# Pure_Power_Strip.net
KiCad netlist of a schematic drawn in EAGLE
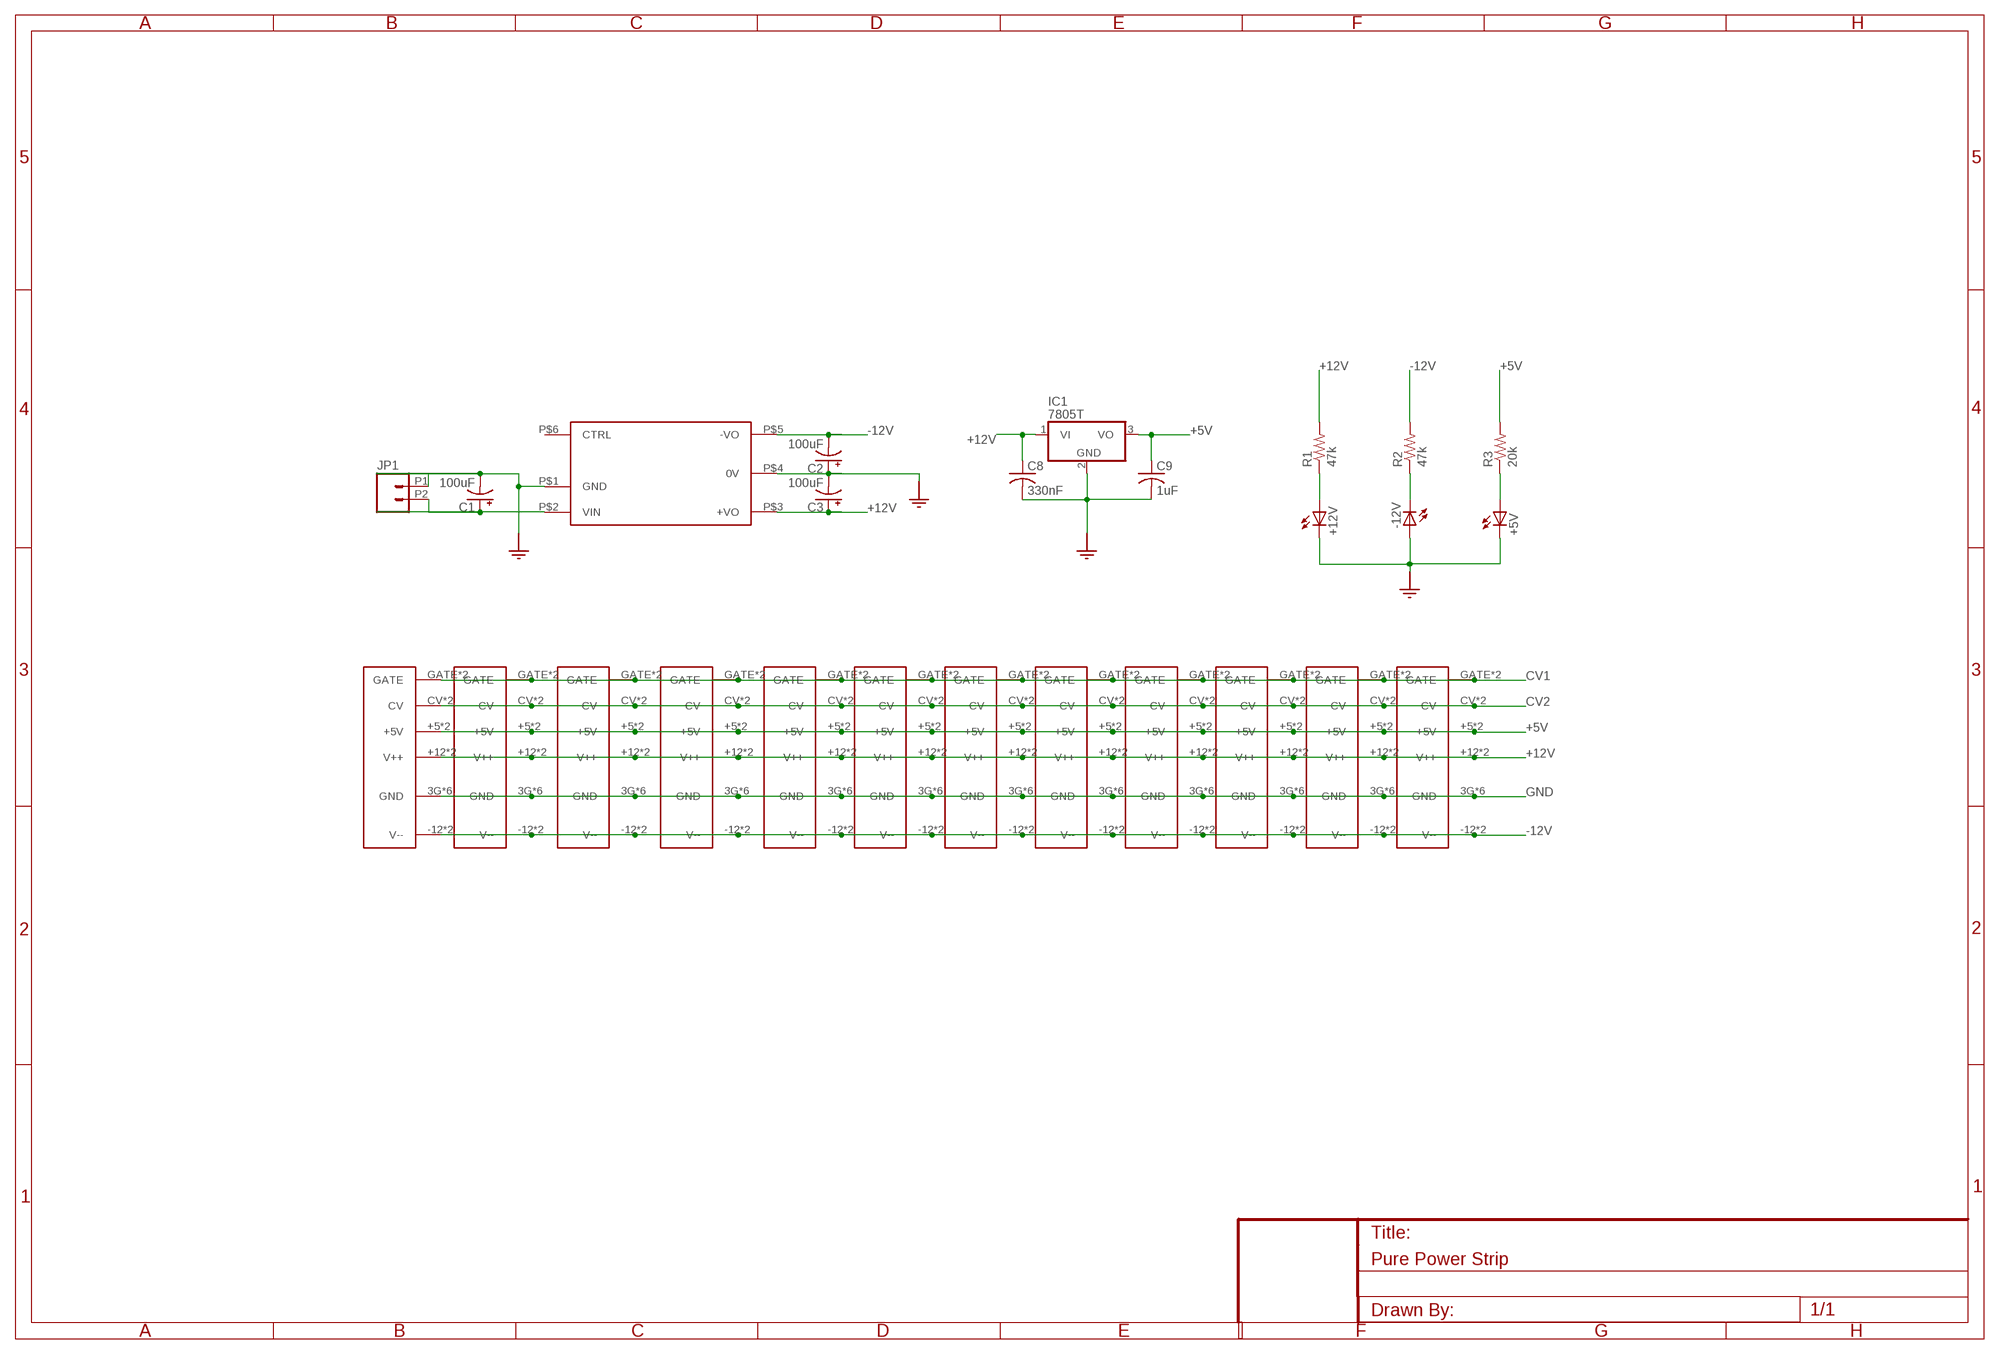
[diagram p0: schematic, sheet 1]

(export (version "E")
  (design (tool "Eeschema 10.0.6"))
  (components
    (comp (ref "+5V")
      (value "LED5MM")
      (footprint "eagle-import:LED5MM")
      (libsource (lib "eagle-import") (part "LED5MM"))
    )
    (comp (ref "+12V")
      (value "LED5MM")
      (footprint "eagle-import:LED5MM")
      (libsource (lib "eagle-import") (part "LED5MM"))
    )
    (comp (ref "-12V")
      (value "LED5MM")
      (footprint "eagle-import:LED5MM")
      (libsource (lib "eagle-import") (part "LED5MM"))
    )
    (comp (ref "C1")
      (value "100uF")
      (footprint "eagle-import:SANYO-OSCON_D")
      (libsource (lib "eagle-import") (part "CPOL-USSANYO_D"))
    )
    (comp (ref "C2")
      (value "100uF")
      (footprint "eagle-import:SANYO-OSCON_D")
      (libsource (lib "eagle-import") (part "CPOL-USSANYO_D"))
    )
    (comp (ref "C3")
      (value "100uF")
      (footprint "eagle-import:SANYO-OSCON_D")
      (libsource (lib "eagle-import") (part "CPOL-USSANYO_D"))
    )
    (comp (ref "C8")
      (value "330nF")
      (footprint "eagle-import:C025-024X044")
      (libsource (lib "eagle-import") (part "C-US025-024X044"))
    )
    (comp (ref "C9")
      (value "1uF")
      (footprint "eagle-import:C025-024X044")
      (libsource (lib "eagle-import") (part "C-US025-024X044"))
    )
    (comp (ref "IC1")
      (value "7805T")
      (footprint "eagle-import:TO220H")
      (libsource (lib "eagle-import") (part "78T05"))
    )
    (comp (ref "JP1")
      (value "1X02_5MM_SCREWTERM")
      (footprint "eagle-import:1X02_5MM_SCREWTERM")
      (libsource (lib "eagle-import") (part "1X02_5MM_SCREWTERM"))
    )
    (comp (ref "R1")
      (value "47k")
      (footprint "eagle-import:0207_10")
      (libsource (lib "eagle-import") (part "R-US_0207/10"))
    )
    (comp (ref "R2")
      (value "47k")
      (footprint "eagle-import:0207_10")
      (libsource (lib "eagle-import") (part "R-US_0207/10"))
    )
    (comp (ref "R3")
      (value "20k")
      (footprint "eagle-import:0207_10")
      (libsource (lib "eagle-import") (part "R-US_0207/10"))
    )
    (comp (ref "U$1")
      (value "URA241XLD-20WR3")
      (footprint "eagle-import:URA241XLD-20WR3")
      (libsource (lib "eagle-import") (part "URA241XLD-20WR3"))
    )
    (comp (ref "U$2")
      (value "EURO_POWER_16")
      (footprint "eagle-import:POWER_SHROUDED")
      (libsource (lib "eagle-import") (part "EURO_POWER_16"))
    )
    (comp (ref "U$3")
      (value "EURO_POWER_16")
      (footprint "eagle-import:POWER_SHROUDED")
      (libsource (lib "eagle-import") (part "EURO_POWER_16"))
    )
    (comp (ref "U$4")
      (value "EURO_POWER_16")
      (footprint "eagle-import:POWER_SHROUDED")
      (libsource (lib "eagle-import") (part "EURO_POWER_16"))
    )
    (comp (ref "U$5")
      (value "EURO_POWER_16")
      (footprint "eagle-import:POWER_SHROUDED")
      (libsource (lib "eagle-import") (part "EURO_POWER_16"))
    )
    (comp (ref "U$6")
      (value "EURO_POWER_16")
      (footprint "eagle-import:POWER_SHROUDED")
      (libsource (lib "eagle-import") (part "EURO_POWER_16"))
    )
    (comp (ref "U$7")
      (value "EURO_POWER_16")
      (footprint "eagle-import:POWER_SHROUDED")
      (libsource (lib "eagle-import") (part "EURO_POWER_16"))
    )
    (comp (ref "U$8")
      (value "EURO_POWER_16")
      (footprint "eagle-import:POWER_SHROUDED")
      (libsource (lib "eagle-import") (part "EURO_POWER_16"))
    )
    (comp (ref "U$9")
      (value "EURO_POWER_16")
      (footprint "eagle-import:POWER_SHROUDED")
      (libsource (lib "eagle-import") (part "EURO_POWER_16"))
    )
    (comp (ref "U$10")
      (value "EURO_POWER_16")
      (footprint "eagle-import:POWER_SHROUDED")
      (libsource (lib "eagle-import") (part "EURO_POWER_16"))
    )
    (comp (ref "U$11")
      (value "EURO_POWER_16")
      (footprint "eagle-import:POWER_SHROUDED")
      (libsource (lib "eagle-import") (part "EURO_POWER_16"))
    )
    (comp (ref "U$12")
      (value "EURO_POWER_16")
      (footprint "eagle-import:POWER_SHROUDED")
      (libsource (lib "eagle-import") (part "EURO_POWER_16"))
    )
    (comp (ref "U$13")
      (value "EURO_POWER_16")
      (footprint "eagle-import:POWER_SHROUDED")
      (libsource (lib "eagle-import") (part "EURO_POWER_16"))
    )
  )
  (nets
    (net (code "1") (name "/+5V") (class "Default")
      (node (ref "C9") (pin "1") (pinfunction "1_1") (pintype "passive"))
      (node (ref "IC1") (pin "3") (pinfunction "VO_3") (pintype "passive"))
      (node (ref "R3") (pin "2") (pinfunction "2_2") (pintype "passive"))
      (node (ref "U$10") (pin "+5") (pinfunction "+5V_+5") (pintype "bidirectional"))
      (node (ref "U$10") (pin "+5A") (pinfunction "+5V_+5A") (pintype "bidirectional"))
      (node (ref "U$11") (pin "+5") (pinfunction "+5V_+5") (pintype "bidirectional"))
      (node (ref "U$11") (pin "+5A") (pinfunction "+5V_+5A") (pintype "bidirectional"))
      (node (ref "U$12") (pin "+5") (pinfunction "+5V_+5") (pintype "bidirectional"))
      (node (ref "U$12") (pin "+5A") (pinfunction "+5V_+5A") (pintype "bidirectional"))
      (node (ref "U$13") (pin "+5") (pinfunction "+5V_+5") (pintype "bidirectional"))
      (node (ref "U$13") (pin "+5A") (pinfunction "+5V_+5A") (pintype "bidirectional"))
      (node (ref "U$2") (pin "+5") (pinfunction "+5V_+5") (pintype "bidirectional"))
      (node (ref "U$2") (pin "+5A") (pinfunction "+5V_+5A") (pintype "bidirectional"))
      (node (ref "U$3") (pin "+5") (pinfunction "+5V_+5") (pintype "bidirectional"))
      (node (ref "U$3") (pin "+5A") (pinfunction "+5V_+5A") (pintype "bidirectional"))
      (node (ref "U$4") (pin "+5") (pinfunction "+5V_+5") (pintype "bidirectional"))
      (node (ref "U$4") (pin "+5A") (pinfunction "+5V_+5A") (pintype "bidirectional"))
      (node (ref "U$5") (pin "+5") (pinfunction "+5V_+5") (pintype "bidirectional"))
      (node (ref "U$5") (pin "+5A") (pinfunction "+5V_+5A") (pintype "bidirectional"))
      (node (ref "U$6") (pin "+5") (pinfunction "+5V_+5") (pintype "bidirectional"))
      (node (ref "U$6") (pin "+5A") (pinfunction "+5V_+5A") (pintype "bidirectional"))
      (node (ref "U$7") (pin "+5") (pinfunction "+5V_+5") (pintype "bidirectional"))
      (node (ref "U$7") (pin "+5A") (pinfunction "+5V_+5A") (pintype "bidirectional"))
      (node (ref "U$8") (pin "+5") (pinfunction "+5V_+5") (pintype "bidirectional"))
      (node (ref "U$8") (pin "+5A") (pinfunction "+5V_+5A") (pintype "bidirectional"))
      (node (ref "U$9") (pin "+5") (pinfunction "+5V_+5") (pintype "bidirectional"))
      (node (ref "U$9") (pin "+5A") (pinfunction "+5V_+5A") (pintype "bidirectional"))
    )
    (net (code "2") (name "/+12V") (class "Default")
      (node (ref "C3") (pin "+") (pinfunction "+_+") (pintype "passive"))
      (node (ref "C8") (pin "1") (pinfunction "1_1") (pintype "passive"))
      (node (ref "IC1") (pin "1") (pinfunction "VI_1") (pintype "input"))
      (node (ref "R1") (pin "2") (pinfunction "2_2") (pintype "passive"))
      (node (ref "U$1") (pin "P$3") (pinfunction "+VO_P$3") (pintype "bidirectional"))
      (node (ref "U$10") (pin "+12") (pinfunction "V++_+12") (pintype "bidirectional"))
      (node (ref "U$10") (pin "+12A") (pinfunction "V++_+12A") (pintype "bidirectional"))
      (node (ref "U$11") (pin "+12") (pinfunction "V++_+12") (pintype "bidirectional"))
      (node (ref "U$11") (pin "+12A") (pinfunction "V++_+12A") (pintype "bidirectional"))
      (node (ref "U$12") (pin "+12") (pinfunction "V++_+12") (pintype "bidirectional"))
      (node (ref "U$12") (pin "+12A") (pinfunction "V++_+12A") (pintype "bidirectional"))
      (node (ref "U$13") (pin "+12") (pinfunction "V++_+12") (pintype "bidirectional"))
      (node (ref "U$13") (pin "+12A") (pinfunction "V++_+12A") (pintype "bidirectional"))
      (node (ref "U$2") (pin "+12") (pinfunction "V++_+12") (pintype "bidirectional"))
      (node (ref "U$2") (pin "+12A") (pinfunction "V++_+12A") (pintype "bidirectional"))
      (node (ref "U$3") (pin "+12") (pinfunction "V++_+12") (pintype "bidirectional"))
      (node (ref "U$3") (pin "+12A") (pinfunction "V++_+12A") (pintype "bidirectional"))
      (node (ref "U$4") (pin "+12") (pinfunction "V++_+12") (pintype "bidirectional"))
      (node (ref "U$4") (pin "+12A") (pinfunction "V++_+12A") (pintype "bidirectional"))
      (node (ref "U$5") (pin "+12") (pinfunction "V++_+12") (pintype "bidirectional"))
      (node (ref "U$5") (pin "+12A") (pinfunction "V++_+12A") (pintype "bidirectional"))
      (node (ref "U$6") (pin "+12") (pinfunction "V++_+12") (pintype "bidirectional"))
      (node (ref "U$6") (pin "+12A") (pinfunction "V++_+12A") (pintype "bidirectional"))
      (node (ref "U$7") (pin "+12") (pinfunction "V++_+12") (pintype "bidirectional"))
      (node (ref "U$7") (pin "+12A") (pinfunction "V++_+12A") (pintype "bidirectional"))
      (node (ref "U$8") (pin "+12") (pinfunction "V++_+12") (pintype "bidirectional"))
      (node (ref "U$8") (pin "+12A") (pinfunction "V++_+12A") (pintype "bidirectional"))
      (node (ref "U$9") (pin "+12") (pinfunction "V++_+12") (pintype "bidirectional"))
      (node (ref "U$9") (pin "+12A") (pinfunction "V++_+12A") (pintype "bidirectional"))
    )
    (net (code "3") (name "/-12V") (class "Default")
      (node (ref "C2") (pin "-") (pinfunction "-_-") (pintype "passive"))
      (node (ref "R2") (pin "2") (pinfunction "2_2") (pintype "passive"))
      (node (ref "U$1") (pin "P$5") (pinfunction "-VO_P$5") (pintype "bidirectional"))
      (node (ref "U$10") (pin "-12") (pinfunction "V--_-12") (pintype "bidirectional"))
      (node (ref "U$10") (pin "-12A") (pinfunction "V--_-12A") (pintype "bidirectional"))
      (node (ref "U$11") (pin "-12") (pinfunction "V--_-12") (pintype "bidirectional"))
      (node (ref "U$11") (pin "-12A") (pinfunction "V--_-12A") (pintype "bidirectional"))
      (node (ref "U$12") (pin "-12") (pinfunction "V--_-12") (pintype "bidirectional"))
      (node (ref "U$12") (pin "-12A") (pinfunction "V--_-12A") (pintype "bidirectional"))
      (node (ref "U$13") (pin "-12") (pinfunction "V--_-12") (pintype "bidirectional"))
      (node (ref "U$13") (pin "-12A") (pinfunction "V--_-12A") (pintype "bidirectional"))
      (node (ref "U$2") (pin "-12") (pinfunction "V--_-12") (pintype "bidirectional"))
      (node (ref "U$2") (pin "-12A") (pinfunction "V--_-12A") (pintype "bidirectional"))
      (node (ref "U$3") (pin "-12") (pinfunction "V--_-12") (pintype "bidirectional"))
      (node (ref "U$3") (pin "-12A") (pinfunction "V--_-12A") (pintype "bidirectional"))
      (node (ref "U$4") (pin "-12") (pinfunction "V--_-12") (pintype "bidirectional"))
      (node (ref "U$4") (pin "-12A") (pinfunction "V--_-12A") (pintype "bidirectional"))
      (node (ref "U$5") (pin "-12") (pinfunction "V--_-12") (pintype "bidirectional"))
      (node (ref "U$5") (pin "-12A") (pinfunction "V--_-12A") (pintype "bidirectional"))
      (node (ref "U$6") (pin "-12") (pinfunction "V--_-12") (pintype "bidirectional"))
      (node (ref "U$6") (pin "-12A") (pinfunction "V--_-12A") (pintype "bidirectional"))
      (node (ref "U$7") (pin "-12") (pinfunction "V--_-12") (pintype "bidirectional"))
      (node (ref "U$7") (pin "-12A") (pinfunction "V--_-12A") (pintype "bidirectional"))
      (node (ref "U$8") (pin "-12") (pinfunction "V--_-12") (pintype "bidirectional"))
      (node (ref "U$8") (pin "-12A") (pinfunction "V--_-12A") (pintype "bidirectional"))
      (node (ref "U$9") (pin "-12") (pinfunction "V--_-12") (pintype "bidirectional"))
      (node (ref "U$9") (pin "-12A") (pinfunction "V--_-12A") (pintype "bidirectional"))
    )
    (net (code "4") (name "/CV1") (class "Default")
      (node (ref "U$10") (pin "GATE") (pinfunction "GATE_GATE") (pintype "bidirectional"))
      (node (ref "U$10") (pin "GATEA") (pinfunction "GATE_GATEA") (pintype "bidirectional"))
      (node (ref "U$11") (pin "GATE") (pinfunction "GATE_GATE") (pintype "bidirectional"))
      (node (ref "U$11") (pin "GATEA") (pinfunction "GATE_GATEA") (pintype "bidirectional"))
      (node (ref "U$12") (pin "GATE") (pinfunction "GATE_GATE") (pintype "bidirectional"))
      (node (ref "U$12") (pin "GATEA") (pinfunction "GATE_GATEA") (pintype "bidirectional"))
      (node (ref "U$13") (pin "GATE") (pinfunction "GATE_GATE") (pintype "bidirectional"))
      (node (ref "U$13") (pin "GATEA") (pinfunction "GATE_GATEA") (pintype "bidirectional"))
      (node (ref "U$2") (pin "GATE") (pinfunction "GATE_GATE") (pintype "bidirectional"))
      (node (ref "U$2") (pin "GATEA") (pinfunction "GATE_GATEA") (pintype "bidirectional"))
      (node (ref "U$3") (pin "GATE") (pinfunction "GATE_GATE") (pintype "bidirectional"))
      (node (ref "U$3") (pin "GATEA") (pinfunction "GATE_GATEA") (pintype "bidirectional"))
      (node (ref "U$4") (pin "GATE") (pinfunction "GATE_GATE") (pintype "bidirectional"))
      (node (ref "U$4") (pin "GATEA") (pinfunction "GATE_GATEA") (pintype "bidirectional"))
      (node (ref "U$5") (pin "GATE") (pinfunction "GATE_GATE") (pintype "bidirectional"))
      (node (ref "U$5") (pin "GATEA") (pinfunction "GATE_GATEA") (pintype "bidirectional"))
      (node (ref "U$6") (pin "GATE") (pinfunction "GATE_GATE") (pintype "bidirectional"))
      (node (ref "U$6") (pin "GATEA") (pinfunction "GATE_GATEA") (pintype "bidirectional"))
      (node (ref "U$7") (pin "GATE") (pinfunction "GATE_GATE") (pintype "bidirectional"))
      (node (ref "U$7") (pin "GATEA") (pinfunction "GATE_GATEA") (pintype "bidirectional"))
      (node (ref "U$8") (pin "GATE") (pinfunction "GATE_GATE") (pintype "bidirectional"))
      (node (ref "U$8") (pin "GATEA") (pinfunction "GATE_GATEA") (pintype "bidirectional"))
      (node (ref "U$9") (pin "GATE") (pinfunction "GATE_GATE") (pintype "bidirectional"))
      (node (ref "U$9") (pin "GATEA") (pinfunction "GATE_GATEA") (pintype "bidirectional"))
    )
    (net (code "5") (name "/CV2") (class "Default")
      (node (ref "U$10") (pin "CV") (pinfunction "CV_CV") (pintype "bidirectional"))
      (node (ref "U$10") (pin "CVA") (pinfunction "CV_CVA") (pintype "bidirectional"))
      (node (ref "U$11") (pin "CV") (pinfunction "CV_CV") (pintype "bidirectional"))
      (node (ref "U$11") (pin "CVA") (pinfunction "CV_CVA") (pintype "bidirectional"))
      (node (ref "U$12") (pin "CV") (pinfunction "CV_CV") (pintype "bidirectional"))
      (node (ref "U$12") (pin "CVA") (pinfunction "CV_CVA") (pintype "bidirectional"))
      (node (ref "U$13") (pin "CV") (pinfunction "CV_CV") (pintype "bidirectional"))
      (node (ref "U$13") (pin "CVA") (pinfunction "CV_CVA") (pintype "bidirectional"))
      (node (ref "U$2") (pin "CV") (pinfunction "CV_CV") (pintype "bidirectional"))
      (node (ref "U$2") (pin "CVA") (pinfunction "CV_CVA") (pintype "bidirectional"))
      (node (ref "U$3") (pin "CV") (pinfunction "CV_CV") (pintype "bidirectional"))
      (node (ref "U$3") (pin "CVA") (pinfunction "CV_CVA") (pintype "bidirectional"))
      (node (ref "U$4") (pin "CV") (pinfunction "CV_CV") (pintype "bidirectional"))
      (node (ref "U$4") (pin "CVA") (pinfunction "CV_CVA") (pintype "bidirectional"))
      (node (ref "U$5") (pin "CV") (pinfunction "CV_CV") (pintype "bidirectional"))
      (node (ref "U$5") (pin "CVA") (pinfunction "CV_CVA") (pintype "bidirectional"))
      (node (ref "U$6") (pin "CV") (pinfunction "CV_CV") (pintype "bidirectional"))
      (node (ref "U$6") (pin "CVA") (pinfunction "CV_CVA") (pintype "bidirectional"))
      (node (ref "U$7") (pin "CV") (pinfunction "CV_CV") (pintype "bidirectional"))
      (node (ref "U$7") (pin "CVA") (pinfunction "CV_CVA") (pintype "bidirectional"))
      (node (ref "U$8") (pin "CV") (pinfunction "CV_CV") (pintype "bidirectional"))
      (node (ref "U$8") (pin "CVA") (pinfunction "CV_CVA") (pintype "bidirectional"))
      (node (ref "U$9") (pin "CV") (pinfunction "CV_CV") (pintype "bidirectional"))
      (node (ref "U$9") (pin "CVA") (pinfunction "CV_CVA") (pintype "bidirectional"))
    )
    (net (code "6") (name "GND") (class "Default")
      (node (ref "+12V") (pin "K") (pinfunction "C_K") (pintype "passive"))
      (node (ref "+5V") (pin "K") (pinfunction "C_K") (pintype "passive"))
      (node (ref "-12V") (pin "A") (pinfunction "A_A") (pintype "passive"))
      (node (ref "C1") (pin "-") (pinfunction "-_-") (pintype "passive"))
      (node (ref "C2") (pin "+") (pinfunction "+_+") (pintype "passive"))
      (node (ref "C3") (pin "-") (pinfunction "-_-") (pintype "passive"))
      (node (ref "C8") (pin "2") (pinfunction "2_2") (pintype "passive"))
      (node (ref "C9") (pin "2") (pinfunction "2_2") (pintype "passive"))
      (node (ref "IC1") (pin "2") (pinfunction "GND_2") (pintype "passive"))
      (node (ref "JP1") (pin "P1") (pinfunction "2_P1") (pintype "passive"))
      (node (ref "U$1") (pin "P$1") (pinfunction "GND_P$1") (pintype "bidirectional"))
      (node (ref "U$1") (pin "P$4") (pinfunction "0V_P$4") (pintype "bidirectional"))
      (node (ref "U$10") (pin "3G") (pinfunction "GND_3G") (pintype "bidirectional"))
      (node (ref "U$10") (pin "4G") (pinfunction "GND_4G") (pintype "bidirectional"))
      (node (ref "U$10") (pin "5G") (pinfunction "GND_5G") (pintype "bidirectional"))
      (node (ref "U$10") (pin "6G") (pinfunction "GND_6G") (pintype "bidirectional"))
      (node (ref "U$10") (pin "7G") (pinfunction "GND_7G") (pintype "bidirectional"))
      (node (ref "U$10") (pin "8G") (pinfunction "GND_8G") (pintype "bidirectional"))
      (node (ref "U$11") (pin "3G") (pinfunction "GND_3G") (pintype "bidirectional"))
      (node (ref "U$11") (pin "4G") (pinfunction "GND_4G") (pintype "bidirectional"))
      (node (ref "U$11") (pin "5G") (pinfunction "GND_5G") (pintype "bidirectional"))
      (node (ref "U$11") (pin "6G") (pinfunction "GND_6G") (pintype "bidirectional"))
      (node (ref "U$11") (pin "7G") (pinfunction "GND_7G") (pintype "bidirectional"))
      (node (ref "U$11") (pin "8G") (pinfunction "GND_8G") (pintype "bidirectional"))
      (node (ref "U$12") (pin "3G") (pinfunction "GND_3G") (pintype "bidirectional"))
      (node (ref "U$12") (pin "4G") (pinfunction "GND_4G") (pintype "bidirectional"))
      (node (ref "U$12") (pin "5G") (pinfunction "GND_5G") (pintype "bidirectional"))
      (node (ref "U$12") (pin "6G") (pinfunction "GND_6G") (pintype "bidirectional"))
      (node (ref "U$12") (pin "7G") (pinfunction "GND_7G") (pintype "bidirectional"))
      (node (ref "U$12") (pin "8G") (pinfunction "GND_8G") (pintype "bidirectional"))
      (node (ref "U$13") (pin "3G") (pinfunction "GND_3G") (pintype "bidirectional"))
      (node (ref "U$13") (pin "4G") (pinfunction "GND_4G") (pintype "bidirectional"))
      (node (ref "U$13") (pin "5G") (pinfunction "GND_5G") (pintype "bidirectional"))
      (node (ref "U$13") (pin "6G") (pinfunction "GND_6G") (pintype "bidirectional"))
      (node (ref "U$13") (pin "7G") (pinfunction "GND_7G") (pintype "bidirectional"))
      (node (ref "U$13") (pin "8G") (pinfunction "GND_8G") (pintype "bidirectional"))
      (node (ref "U$2") (pin "3G") (pinfunction "GND_3G") (pintype "bidirectional"))
      (node (ref "U$2") (pin "4G") (pinfunction "GND_4G") (pintype "bidirectional"))
      (node (ref "U$2") (pin "5G") (pinfunction "GND_5G") (pintype "bidirectional"))
      (node (ref "U$2") (pin "6G") (pinfunction "GND_6G") (pintype "bidirectional"))
      (node (ref "U$2") (pin "7G") (pinfunction "GND_7G") (pintype "bidirectional"))
      (node (ref "U$2") (pin "8G") (pinfunction "GND_8G") (pintype "bidirectional"))
      (node (ref "U$3") (pin "3G") (pinfunction "GND_3G") (pintype "bidirectional"))
      (node (ref "U$3") (pin "4G") (pinfunction "GND_4G") (pintype "bidirectional"))
      (node (ref "U$3") (pin "5G") (pinfunction "GND_5G") (pintype "bidirectional"))
      (node (ref "U$3") (pin "6G") (pinfunction "GND_6G") (pintype "bidirectional"))
      (node (ref "U$3") (pin "7G") (pinfunction "GND_7G") (pintype "bidirectional"))
      (node (ref "U$3") (pin "8G") (pinfunction "GND_8G") (pintype "bidirectional"))
      (node (ref "U$4") (pin "3G") (pinfunction "GND_3G") (pintype "bidirectional"))
      (node (ref "U$4") (pin "4G") (pinfunction "GND_4G") (pintype "bidirectional"))
      (node (ref "U$4") (pin "5G") (pinfunction "GND_5G") (pintype "bidirectional"))
      (node (ref "U$4") (pin "6G") (pinfunction "GND_6G") (pintype "bidirectional"))
      (node (ref "U$4") (pin "7G") (pinfunction "GND_7G") (pintype "bidirectional"))
      (node (ref "U$4") (pin "8G") (pinfunction "GND_8G") (pintype "bidirectional"))
      (node (ref "U$5") (pin "3G") (pinfunction "GND_3G") (pintype "bidirectional"))
      (node (ref "U$5") (pin "4G") (pinfunction "GND_4G") (pintype "bidirectional"))
      (node (ref "U$5") (pin "5G") (pinfunction "GND_5G") (pintype "bidirectional"))
      (node (ref "U$5") (pin "6G") (pinfunction "GND_6G") (pintype "bidirectional"))
      (node (ref "U$5") (pin "7G") (pinfunction "GND_7G") (pintype "bidirectional"))
      (node (ref "U$5") (pin "8G") (pinfunction "GND_8G") (pintype "bidirectional"))
      (node (ref "U$6") (pin "3G") (pinfunction "GND_3G") (pintype "bidirectional"))
      (node (ref "U$6") (pin "4G") (pinfunction "GND_4G") (pintype "bidirectional"))
      (node (ref "U$6") (pin "5G") (pinfunction "GND_5G") (pintype "bidirectional"))
      (node (ref "U$6") (pin "6G") (pinfunction "GND_6G") (pintype "bidirectional"))
      (node (ref "U$6") (pin "7G") (pinfunction "GND_7G") (pintype "bidirectional"))
      (node (ref "U$6") (pin "8G") (pinfunction "GND_8G") (pintype "bidirectional"))
      (node (ref "U$7") (pin "3G") (pinfunction "GND_3G") (pintype "bidirectional"))
      (node (ref "U$7") (pin "4G") (pinfunction "GND_4G") (pintype "bidirectional"))
      (node (ref "U$7") (pin "5G") (pinfunction "GND_5G") (pintype "bidirectional"))
      (node (ref "U$7") (pin "6G") (pinfunction "GND_6G") (pintype "bidirectional"))
      (node (ref "U$7") (pin "7G") (pinfunction "GND_7G") (pintype "bidirectional"))
      (node (ref "U$7") (pin "8G") (pinfunction "GND_8G") (pintype "bidirectional"))
      (node (ref "U$8") (pin "3G") (pinfunction "GND_3G") (pintype "bidirectional"))
      (node (ref "U$8") (pin "4G") (pinfunction "GND_4G") (pintype "bidirectional"))
      (node (ref "U$8") (pin "5G") (pinfunction "GND_5G") (pintype "bidirectional"))
      (node (ref "U$8") (pin "6G") (pinfunction "GND_6G") (pintype "bidirectional"))
      (node (ref "U$8") (pin "7G") (pinfunction "GND_7G") (pintype "bidirectional"))
      (node (ref "U$8") (pin "8G") (pinfunction "GND_8G") (pintype "bidirectional"))
      (node (ref "U$9") (pin "3G") (pinfunction "GND_3G") (pintype "bidirectional"))
      (node (ref "U$9") (pin "4G") (pinfunction "GND_4G") (pintype "bidirectional"))
      (node (ref "U$9") (pin "5G") (pinfunction "GND_5G") (pintype "bidirectional"))
      (node (ref "U$9") (pin "6G") (pinfunction "GND_6G") (pintype "bidirectional"))
      (node (ref "U$9") (pin "7G") (pinfunction "GND_7G") (pintype "bidirectional"))
      (node (ref "U$9") (pin "8G") (pinfunction "GND_8G") (pintype "bidirectional"))
    )
    (net (code "7") (name "Net-(+5V-PadA)") (class "Default")
      (node (ref "+5V") (pin "A") (pinfunction "A_A") (pintype "passive"))
      (node (ref "R3") (pin "1") (pinfunction "1_1") (pintype "passive"))
    )
    (net (code "8") (name "Net-(+12V-PadA)") (class "Default")
      (node (ref "+12V") (pin "A") (pinfunction "A_A") (pintype "passive"))
      (node (ref "R1") (pin "1") (pinfunction "1_1") (pintype "passive"))
    )
    (net (code "9") (name "Net-(-12V-C)") (class "Default")
      (node (ref "-12V") (pin "K") (pinfunction "C_K") (pintype "passive"))
      (node (ref "R2") (pin "1") (pinfunction "1_1") (pintype "passive"))
    )
    (net (code "10") (name "Net-(JP1-1)") (class "Default")
      (node (ref "C1") (pin "+") (pinfunction "+_+") (pintype "passive"))
      (node (ref "JP1") (pin "P2") (pinfunction "1_P2") (pintype "passive"))
      (node (ref "U$1") (pin "P$2") (pinfunction "VIN_P$2") (pintype "bidirectional"))
    )
    (net (code "11") (name "unconnected-(U$1-CTRL-PadP$6)") (class "Default")
      (node (ref "U$1") (pin "P$6") (pinfunction "CTRL_P$6") (pintype "bidirectional"))
    )
  )
)
